# 411_1st_schematic.net
KiCad netlist of a schematic drawn in EAGLE
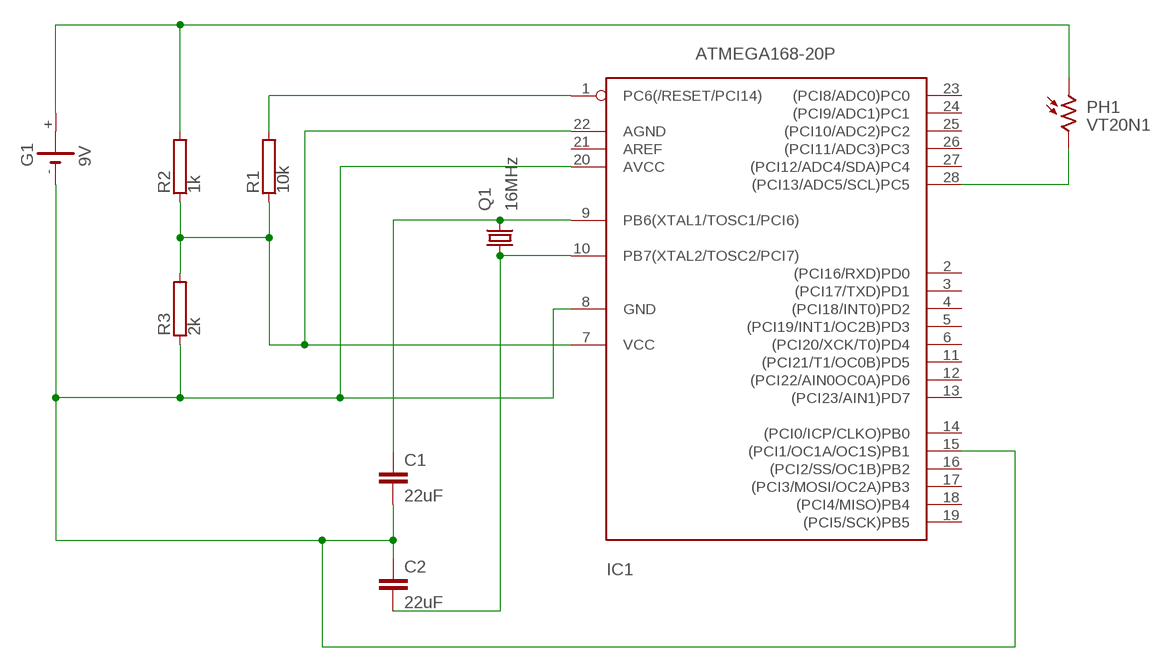
[diagram p0: schematic, sheet 1]

(export (version "E")
  (design (tool "Eeschema 10.0.6"))
  (components
    (comp (ref "C1")
      (value "22uF")
      (footprint "eagle-import:C2.5-3")
      (libsource (lib "eagle-import") (part "C2,5-3"))
    )
    (comp (ref "C2")
      (value "22uF")
      (footprint "eagle-import:C2.5-3")
      (libsource (lib "eagle-import") (part "C2,5-3"))
    )
    (comp (ref "G1")
      (value "9V")
      (footprint "eagle-import:1V60R")
      (libsource (lib "eagle-import") (part "1V60R"))
    )
    (comp (ref "IC1")
      (value "ATMEGA168-20P")
      (footprint "eagle-import:DIL28-3")
      (libsource (lib "eagle-import") (part "ATMEGA168P-20"))
    )
    (comp (ref "PH1")
      (value "VT20N1")
      (footprint "eagle-import:TO46-VT200")
      (libsource (lib "eagle-import") (part "VT20N1"))
    )
    (comp (ref "Q1")
      (value "16MHz")
      (footprint "eagle-import:2.5X2.0_KX-6")
      (libsource (lib "eagle-import") (part "KX-6"))
    )
    (comp (ref "R1")
      (value "10k")
      (footprint "eagle-import:AC01")
      (libsource (lib "eagle-import") (part "RAC01"))
    )
    (comp (ref "R2")
      (value "1k")
      (footprint "eagle-import:AC01")
      (libsource (lib "eagle-import") (part "RAC01"))
    )
    (comp (ref "R3")
      (value "2k")
      (footprint "eagle-import:AC01")
      (libsource (lib "eagle-import") (part "RAC01"))
    )
  )
  (nets
    (net (code "1") (name "Net-(G1-Pad+)") (class "Default")
      (node (ref "G1") (pin "+") (pinfunction "+_+") (pintype "passive"))
      (node (ref "PH1") (pin "1") (pinfunction "1_1") (pintype "passive"))
      (node (ref "R2") (pin "2") (pinfunction "2_2") (pintype "passive"))
    )
    (net (code "2") (name "Net-(IC1-(PCI1{slash}OC1A{slash}OC1S)PB1)") (class "Default")
      (node (ref "C1") (pin "2") (pinfunction "2_2") (pintype "passive"))
      (node (ref "C2") (pin "1") (pinfunction "1_1") (pintype "passive"))
      (node (ref "G1") (pin "-") (pinfunction "-_-") (pintype "passive"))
      (node (ref "IC1") (pin "15") (pinfunction "(PCI1/OC1A/OC1S)PB1_15") (pintype "bidirectional"))
      (node (ref "IC1") (pin "20") (pinfunction "AVCC_20") (pintype "bidirectional"))
      (node (ref "IC1") (pin "8") (pinfunction "GND_8") (pintype "bidirectional"))
      (node (ref "R3") (pin "1") (pinfunction "1_1") (pintype "passive"))
    )
    (net (code "3") (name "Net-(IC1-(PCI13{slash}ADC5{slash}SCL)PC5)") (class "Default")
      (node (ref "IC1") (pin "28") (pinfunction "(PCI13/ADC5/SCL)PC5_28") (pintype "bidirectional"))
      (node (ref "PH1") (pin "2") (pinfunction "2_2") (pintype "passive"))
    )
    (net (code "4") (name "Net-(IC1-AGND)") (class "Default")
      (node (ref "IC1") (pin "22") (pinfunction "AGND_22") (pintype "bidirectional"))
      (node (ref "IC1") (pin "7") (pinfunction "VCC_7") (pintype "bidirectional"))
      (node (ref "R1") (pin "1") (pinfunction "1_1") (pintype "passive"))
      (node (ref "R2") (pin "1") (pinfunction "1_1") (pintype "passive"))
      (node (ref "R3") (pin "2") (pinfunction "2_2") (pintype "passive"))
    )
    (net (code "5") (name "Net-(IC1-PB6(XTAL1{slash}TOSC1{slash}PCI6))") (class "Default")
      (node (ref "C1") (pin "1") (pinfunction "1_1") (pintype "passive"))
      (node (ref "IC1") (pin "9") (pinfunction "PB6(XTAL1/TOSC1/PCI6)_9") (pintype "bidirectional"))
      (node (ref "Q1") (pin "3") (pinfunction "2_3") (pintype "passive"))
    )
    (net (code "6") (name "Net-(IC1-PB7(XTAL2{slash}TOSC2{slash}PCI7))") (class "Default")
      (node (ref "C2") (pin "2") (pinfunction "2_2") (pintype "passive"))
      (node (ref "IC1") (pin "10") (pinfunction "PB7(XTAL2/TOSC2/PCI7)_10") (pintype "bidirectional"))
      (node (ref "Q1") (pin "1") (pinfunction "1_1") (pintype "passive"))
    )
    (net (code "7") (name "Net-(IC1-PC6({slash}RESET{slash}PCI14))") (class "Default")
      (node (ref "IC1") (pin "1") (pinfunction "PC6(/RESET/PCI14)_1") (pintype "bidirectional"))
      (node (ref "R1") (pin "2") (pinfunction "2_2") (pintype "passive"))
    )
    (net (code "8") (name "unconnected-(G1-+-Pad+@1)") (class "Default")
      (node (ref "G1") (pin "+@1") (pinfunction "+_+@1") (pintype "passive"))
    )
    (net (code "9") (name "unconnected-(IC1-(PCI0{slash}ICP{slash}CLKO)PB0-Pad14)") (class "Default")
      (node (ref "IC1") (pin "14") (pinfunction "(PCI0/ICP/CLKO)PB0_14") (pintype "bidirectional"))
    )
    (net (code "10") (name "unconnected-(IC1-(PCI2{slash}SS{slash}OC1B)PB2-Pad16)") (class "Default")
      (node (ref "IC1") (pin "16") (pinfunction "(PCI2/SS/OC1B)PB2_16") (pintype "bidirectional"))
    )
    (net (code "11") (name "unconnected-(IC1-(PCI3{slash}MOSI{slash}OC2A)PB3-Pad17)") (class "Default")
      (node (ref "IC1") (pin "17") (pinfunction "(PCI3/MOSI/OC2A)PB3_17") (pintype "bidirectional"))
    )
    (net (code "12") (name "unconnected-(IC1-(PCI4{slash}MISO)PB4-Pad18)") (class "Default")
      (node (ref "IC1") (pin "18") (pinfunction "(PCI4/MISO)PB4_18") (pintype "bidirectional"))
    )
    (net (code "13") (name "unconnected-(IC1-(PCI5{slash}SCK)PB5-Pad19)") (class "Default")
      (node (ref "IC1") (pin "19") (pinfunction "(PCI5/SCK)PB5_19") (pintype "bidirectional"))
    )
    (net (code "14") (name "unconnected-(IC1-(PCI8{slash}ADC0)PC0-Pad23)") (class "Default")
      (node (ref "IC1") (pin "23") (pinfunction "(PCI8/ADC0)PC0_23") (pintype "bidirectional"))
    )
    (net (code "15") (name "unconnected-(IC1-(PCI9{slash}ADC1)PC1-Pad24)") (class "Default")
      (node (ref "IC1") (pin "24") (pinfunction "(PCI9/ADC1)PC1_24") (pintype "bidirectional"))
    )
    (net (code "16") (name "unconnected-(IC1-(PCI10{slash}ADC2)PC2-Pad25)") (class "Default")
      (node (ref "IC1") (pin "25") (pinfunction "(PCI10/ADC2)PC2_25") (pintype "bidirectional"))
    )
    (net (code "17") (name "unconnected-(IC1-(PCI11{slash}ADC3)PC3-Pad26)") (class "Default")
      (node (ref "IC1") (pin "26") (pinfunction "(PCI11/ADC3)PC3_26") (pintype "bidirectional"))
    )
    (net (code "18") (name "unconnected-(IC1-(PCI12{slash}ADC4{slash}SDA)PC4-Pad27)") (class "Default")
      (node (ref "IC1") (pin "27") (pinfunction "(PCI12/ADC4/SDA)PC4_27") (pintype "bidirectional"))
    )
    (net (code "19") (name "unconnected-(IC1-(PCI16{slash}RXD)PD0-Pad2)") (class "Default")
      (node (ref "IC1") (pin "2") (pinfunction "(PCI16/RXD)PD0_2") (pintype "bidirectional"))
    )
    (net (code "20") (name "unconnected-(IC1-(PCI17{slash}TXD)PD1-Pad3)") (class "Default")
      (node (ref "IC1") (pin "3") (pinfunction "(PCI17/TXD)PD1_3") (pintype "bidirectional"))
    )
    (net (code "21") (name "unconnected-(IC1-(PCI18{slash}INT0)PD2-Pad4)") (class "Default")
      (node (ref "IC1") (pin "4") (pinfunction "(PCI18/INT0)PD2_4") (pintype "bidirectional"))
    )
    (net (code "22") (name "unconnected-(IC1-(PCI19{slash}INT1{slash}OC2B)PD3-Pad5)") (class "Default")
      (node (ref "IC1") (pin "5") (pinfunction "(PCI19/INT1/OC2B)PD3_5") (pintype "bidirectional"))
    )
    (net (code "23") (name "unconnected-(IC1-(PCI20{slash}XCK{slash}T0)PD4-Pad6)") (class "Default")
      (node (ref "IC1") (pin "6") (pinfunction "(PCI20/XCK/T0)PD4_6") (pintype "bidirectional"))
    )
    (net (code "24") (name "unconnected-(IC1-(PCI21{slash}T1{slash}OC0B)PD5-Pad11)") (class "Default")
      (node (ref "IC1") (pin "11") (pinfunction "(PCI21/T1/OC0B)PD5_11") (pintype "bidirectional"))
    )
    (net (code "25") (name "unconnected-(IC1-(PCI22{slash}AIN0OC0A)PD6-Pad12)") (class "Default")
      (node (ref "IC1") (pin "12") (pinfunction "(PCI22/AIN0OC0A)PD6_12") (pintype "bidirectional"))
    )
    (net (code "26") (name "unconnected-(IC1-(PCI23{slash}AIN1)PD7-Pad13)") (class "Default")
      (node (ref "IC1") (pin "13") (pinfunction "(PCI23/AIN1)PD7_13") (pintype "bidirectional"))
    )
    (net (code "27") (name "unconnected-(IC1-AREF-Pad21)") (class "Default")
      (node (ref "IC1") (pin "21") (pinfunction "AREF_21") (pintype "bidirectional"))
    )
  )
)
